# Sheet2.net
KiCad netlist of a schematic drawn in Altium Designer
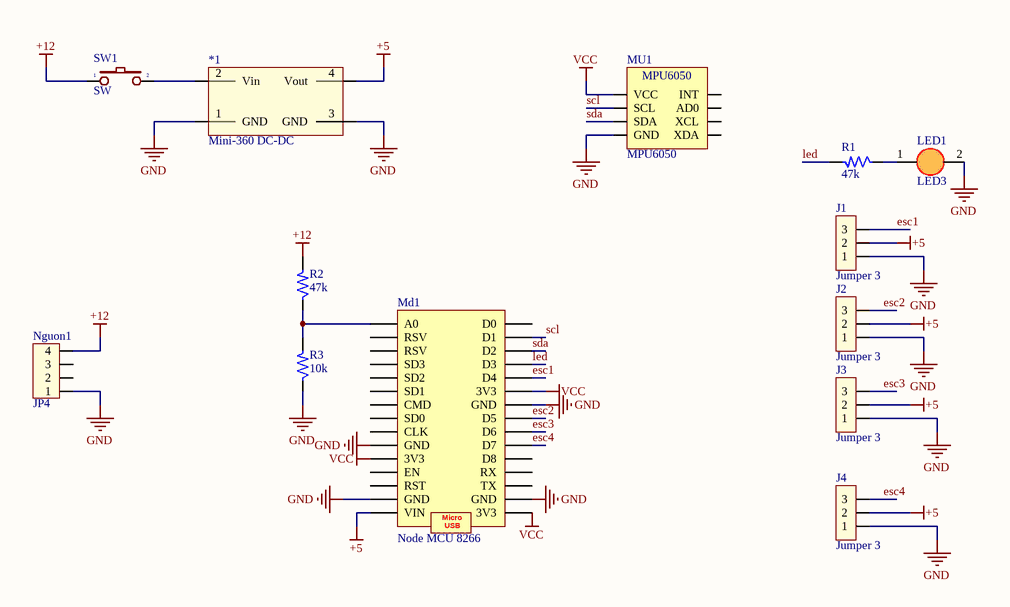
[diagram p0: Sheet2.SchDoc]

(export (version "E")
  (design (tool "Eeschema 10.0.6"))
  (components
    (comp (ref "*1")
      (value "Mini-360 DC-DC")
      (footprint "Mini-360")
      (libsource (lib "AltiumLibraryDDT") (part "Mini-360 DC-DC"))
    )
    (comp (ref "J1") (value "Jumper 3") (footprint "JP3") (libsource (lib "My Library") (part "JP3")))
    (comp (ref "J2") (value "Jumper 3") (footprint "JP3") (libsource (lib "My Library") (part "JP3")))
    (comp (ref "J3") (value "Jumper 3") (footprint "JP3") (libsource (lib "My Library") (part "JP3")))
    (comp (ref "J4") (value "Jumper 3") (footprint "JP3") (libsource (lib "My Library") (part "JP3")))
    (comp (ref "LED1")
      (value "LED3")
      (footprint "LED3mm")
      (description "LED 3mm")
      (libsource (lib "My Library") (part "LED 3mm"))
    )
    (comp (ref "Md1")
      (value "Node MCU 8266")
      (footprint "NODEMCU_ESP8266_CH340")
      (libsource (lib "DaoTakIsaac") (part "NodeMCU_ESP8266"))
    )
    (comp (ref "MU1")
      (value "MPU6050")
      (footprint "MPU6050")
      (fields
        (field (name "MANUFACTURER") "Würth Elektronik eiSos GmbH")
        (field (name "PARTNO") "613004143121")
        (field (name "CREATED BY") "Karrer Zheng")
      )
      (libsource (lib "My Library") (part "MPU6050"))
    )
    (comp (ref "Nguon1")
      (value "JP4")
      (footprint "CON4")
      (description "Connector 4")
      (libsource (lib "My Library") (part "Con4"))
    )
    (comp (ref "R1")
      (value "47k")
      (footprint "R1/8W")
      (description "Resistor 1/4W")
      (libsource (lib "My Library") (part "R"))
    )
    (comp (ref "R2")
      (value "47k")
      (footprint "R1/8W")
      (description "Resistor 1/4W")
      (libsource (lib "My Library") (part "R"))
    )
    (comp (ref "R3")
      (value "10k")
      (footprint "R1/8W")
      (description "Resistor 1/4W")
      (libsource (lib "My Library") (part "R"))
    )
    (comp (ref "SW1")
      (value "SW")
      (footprint "SW2")
      (description "Switch button 2 pin")
      (libsource (lib "My Library") (part "SW2"))
    )
  )
  (nets
    (net (code "1") (name "+5") (class "Default")
      (node (ref "*1") (pin "4") (pinfunction "Vout_4") (pintype "power_in"))
      (node (ref "J1") (pin "2") (pinfunction "2_2") (pintype "passive"))
      (node (ref "J2") (pin "2") (pinfunction "2_2") (pintype "passive"))
      (node (ref "J3") (pin "2") (pinfunction "2_2") (pintype "passive"))
      (node (ref "J4") (pin "2") (pinfunction "2_2") (pintype "passive"))
      (node (ref "Md1") (pin "VIN") (pinfunction "VIN_VIN") (pintype "passive"))
    )
    (net (code "2") (name "+12") (class "Default")
      (node (ref "Nguon1") (pin "4") (pinfunction "4_4") (pintype "passive"))
      (node (ref "R2") (pin "2") (pinfunction "2_2") (pintype "passive"))
      (node (ref "SW1") (pin "1") (pinfunction "1_1") (pintype "passive"))
    )
    (net (code "3") (name "/esc1") (class "Default")
      (node (ref "J1") (pin "3") (pinfunction "3_3") (pintype "passive"))
      (node (ref "Md1") (pin "D4") (pinfunction "D4_D4") (pintype "passive"))
    )
    (net (code "4") (name "/esc2") (class "Default")
      (node (ref "J2") (pin "3") (pinfunction "3_3") (pintype "passive"))
      (node (ref "Md1") (pin "D5") (pinfunction "D5_D5") (pintype "passive"))
    )
    (net (code "5") (name "/esc3") (class "Default")
      (node (ref "J3") (pin "3") (pinfunction "3_3") (pintype "passive"))
      (node (ref "Md1") (pin "D6") (pinfunction "D6_D6") (pintype "passive"))
    )
    (net (code "6") (name "/esc4") (class "Default")
      (node (ref "J4") (pin "3") (pinfunction "3_3") (pintype "passive"))
      (node (ref "Md1") (pin "D7") (pinfunction "D7_D7") (pintype "passive"))
    )
    (net (code "7") (name "/led") (class "Default")
      (node (ref "Md1") (pin "D3") (pinfunction "D3_D3") (pintype "passive"))
      (node (ref "R1") (pin "2") (pinfunction "2_2") (pintype "passive"))
    )
    (net (code "8") (name "/scl") (class "Default")
      (node (ref "MU1") (pin "3") (pinfunction "SCL_3") (pintype "passive"))
      (node (ref "Md1") (pin "D1") (pinfunction "D1_D1") (pintype "passive"))
    )
    (net (code "9") (name "/sda") (class "Default")
      (node (ref "MU1") (pin "4") (pinfunction "SDA_4") (pintype "passive"))
      (node (ref "Md1") (pin "D2") (pinfunction "D2_D2") (pintype "passive"))
    )
    (net (code "10") (name "GND") (class "Default")
      (node (ref "*1") (pin "1") (pinfunction "GND_1") (pintype "power_in"))
      (node (ref "*1") (pin "3") (pinfunction "GND_3") (pintype "power_in"))
      (node (ref "J1") (pin "1") (pinfunction "1_1") (pintype "passive"))
      (node (ref "J2") (pin "1") (pinfunction "1_1") (pintype "passive"))
      (node (ref "J3") (pin "1") (pinfunction "1_1") (pintype "passive"))
      (node (ref "J4") (pin "1") (pinfunction "1_1") (pintype "passive"))
      (node (ref "LED1") (pin "2") (pinfunction "K_2") (pintype "passive"))
      (node (ref "MU1") (pin "2") (pinfunction "GND_2") (pintype "passive"))
      (node (ref "Md1") (pin "GND") (pinfunction "GND_GND") (pintype "passive"))
      (node (ref "Nguon1") (pin "1") (pinfunction "1_1") (pintype "passive"))
      (node (ref "R3") (pin "1") (pinfunction "1_1") (pintype "passive"))
    )
    (net (code "11") (name "Net-(*1-Vin)") (class "Default")
      (node (ref "*1") (pin "2") (pinfunction "Vin_2") (pintype "power_in"))
      (node (ref "SW1") (pin "2") (pinfunction "2_2") (pintype "passive"))
    )
    (net (code "12") (name "Net-(LED1-A)") (class "Default")
      (node (ref "LED1") (pin "1") (pinfunction "A_1") (pintype "passive"))
      (node (ref "R1") (pin "1") (pinfunction "1_1") (pintype "passive"))
    )
    (net (code "13") (name "Net-(Md1-PadA0)") (class "Default")
      (node (ref "Md1") (pin "A0") (pinfunction "A0_A0") (pintype "passive"))
      (node (ref "R2") (pin "1") (pinfunction "1_1") (pintype "passive"))
      (node (ref "R3") (pin "2") (pinfunction "2_2") (pintype "passive"))
    )
    (net (code "14") (name "VCC") (class "Default")
      (node (ref "MU1") (pin "1") (pinfunction "VCC_1") (pintype "passive"))
      (node (ref "Md1") (pin "3V3") (pinfunction "3V3_3V3") (pintype "passive"))
    )
    (net (code "15") (name "unconnected-(MU1-AD0-Pad7)") (class "Default")
      (node (ref "MU1") (pin "7") (pinfunction "AD0_7") (pintype "passive"))
    )
    (net (code "16") (name "unconnected-(MU1-INT-Pad8)") (class "Default")
      (node (ref "MU1") (pin "8") (pinfunction "INT_8") (pintype "passive"))
    )
    (net (code "17") (name "unconnected-(MU1-XCL-Pad6)") (class "Default")
      (node (ref "MU1") (pin "6") (pinfunction "XCL_6") (pintype "passive"))
    )
    (net (code "18") (name "unconnected-(MU1-XDA-Pad5)") (class "Default")
      (node (ref "MU1") (pin "5") (pinfunction "XDA_5") (pintype "passive"))
    )
    (net (code "19") (name "unconnected-(Md1-PadCLK)") (class "Default")
      (node (ref "Md1") (pin "CLK") (pinfunction "CLK_CLK") (pintype "passive"))
    )
    (net (code "20") (name "unconnected-(Md1-PadCMD)") (class "Default")
      (node (ref "Md1") (pin "CMD") (pinfunction "CMD_CMD") (pintype "passive"))
    )
    (net (code "21") (name "unconnected-(Md1-PadD0)") (class "Default")
      (node (ref "Md1") (pin "D0") (pinfunction "D0_D0") (pintype "passive"))
    )
    (net (code "22") (name "unconnected-(Md1-PadD8)") (class "Default")
      (node (ref "Md1") (pin "D8") (pinfunction "D8_D8") (pintype "passive"))
    )
    (net (code "23") (name "unconnected-(Md1-PadEN)") (class "Default")
      (node (ref "Md1") (pin "EN") (pinfunction "EN_EN") (pintype "passive"))
    )
    (net (code "24") (name "unconnected-(Md1-PadRST)") (class "Default")
      (node (ref "Md1") (pin "RST") (pinfunction "RST_RST") (pintype "passive"))
    )
    (net (code "25") (name "unconnected-(Md1-PadRSV)") (class "Default")
      (node (ref "Md1") (pin "RSV") (pinfunction "RSV_RSV") (pintype "passive"))
    )
    (net (code "26") (name "unconnected-(Md1-PadRSV)_1") (class "Default")
      (node (ref "Md1") (pin "RSV") (pinfunction "RSV_RSV") (pintype "passive"))
    )
    (net (code "27") (name "unconnected-(Md1-PadRX)") (class "Default")
      (node (ref "Md1") (pin "RX") (pinfunction "RX_RX") (pintype "passive"))
    )
    (net (code "28") (name "unconnected-(Md1-PadSD0)") (class "Default")
      (node (ref "Md1") (pin "SD0") (pinfunction "SD0_SD0") (pintype "passive"))
    )
    (net (code "29") (name "unconnected-(Md1-PadSD1)") (class "Default")
      (node (ref "Md1") (pin "SD1") (pinfunction "SD1_SD1") (pintype "passive"))
    )
    (net (code "30") (name "unconnected-(Md1-PadSD2)") (class "Default")
      (node (ref "Md1") (pin "SD2") (pinfunction "SD2_SD2") (pintype "passive"))
    )
    (net (code "31") (name "unconnected-(Md1-PadSD3)") (class "Default")
      (node (ref "Md1") (pin "SD3") (pinfunction "SD3_SD3") (pintype "passive"))
    )
    (net (code "32") (name "unconnected-(Md1-PadTX)") (class "Default")
      (node (ref "Md1") (pin "TX") (pinfunction "TX_TX") (pintype "passive"))
    )
    (net (code "33") (name "unconnected-(Nguon1-Pad2)") (class "Default")
      (node (ref "Nguon1") (pin "2") (pinfunction "2_2") (pintype "passive"))
    )
    (net (code "34") (name "unconnected-(Nguon1-Pad3)") (class "Default")
      (node (ref "Nguon1") (pin "3") (pinfunction "3_3") (pintype "passive"))
    )
  )
)
